# power.net
KiCad netlist of a schematic drawn in Altium Designer
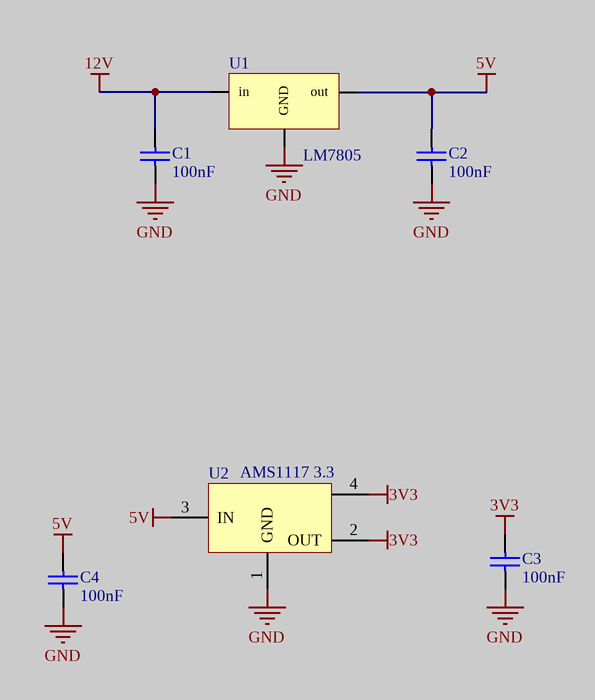
[diagram p0: power.SchDoc]

(export (version "E")
  (design (tool "Eeschema 10.0.6"))
  (components
    (comp (ref "C1")
      (value "100nF")
      (footprint "CAPC0603")
      (description "Capacitor")
      (fields (field (name "PUBLISHER") "Altium Limited"))
      (libsource (lib "eLIB") (part "Capacitor"))
    )
    (comp (ref "C2")
      (value "100nF")
      (footprint "CAPC0603")
      (description "Capacitor")
      (fields (field (name "PUBLISHER") "Altium Limited"))
      (libsource (lib "eLIB") (part "Capacitor"))
    )
    (comp (ref "C3")
      (value "100nF")
      (footprint "CAPC0603")
      (description "Capacitor")
      (fields (field (name "PUBLISHER") "Altium Limited"))
      (libsource (lib "eLIB") (part "Capacitor"))
    )
    (comp (ref "C4")
      (value "100nF")
      (footprint "CAPC0603")
      (description "Capacitor")
      (fields (field (name "PUBLISHER") "Altium Limited"))
      (libsource (lib "eLIB") (part "Capacitor"))
    )
    (comp (ref "U1")
      (value "LM7805")
      (footprint "D2PAK")
      (description "IC REG LIN 5V 1A")
      (libsource (lib "eLIB") (part "LM7805"))
    )
    (comp (ref "U2") (value "AMS1117 3.3") (footprint "AMS1117") (libsource (lib "SINA") (part "AMS1117")))
  )
  (nets
    (net (code "1") (name "3V3") (class "Default")
      (node (ref "C3") (pin "2") (pinfunction "2_2") (pintype "passive"))
      (node (ref "U2") (pin "2") (pinfunction "OUT_2") (pintype "passive"))
      (node (ref "U2") (pin "4") (pinfunction "65_4") (pintype "passive"))
    )
    (net (code "2") (name "5V") (class "Default")
      (node (ref "C2") (pin "2") (pinfunction "2_2") (pintype "passive"))
      (node (ref "C4") (pin "2") (pinfunction "2_2") (pintype "passive"))
      (node (ref "U1") (pin "3") (pinfunction "out_3") (pintype "passive"))
      (node (ref "U2") (pin "3") (pinfunction "IN_3") (pintype "passive"))
    )
    (net (code "3") (name "12V") (class "Default")
      (node (ref "C1") (pin "2") (pinfunction "2_2") (pintype "passive"))
      (node (ref "U1") (pin "1") (pinfunction "in_1") (pintype "passive"))
    )
    (net (code "4") (name "GND") (class "Default")
      (node (ref "C1") (pin "1") (pinfunction "1_1") (pintype "passive"))
      (node (ref "C2") (pin "1") (pinfunction "1_1") (pintype "passive"))
      (node (ref "C3") (pin "1") (pinfunction "1_1") (pintype "passive"))
      (node (ref "C4") (pin "1") (pinfunction "1_1") (pintype "passive"))
      (node (ref "U1") (pin "2") (pinfunction "GND_2") (pintype "passive"))
      (node (ref "U2") (pin "1") (pinfunction "GND_1") (pintype "passive"))
    )
  )
)
